# CON_PCIe_X4.net
KiCad netlist of a schematic drawn in Altium Designer
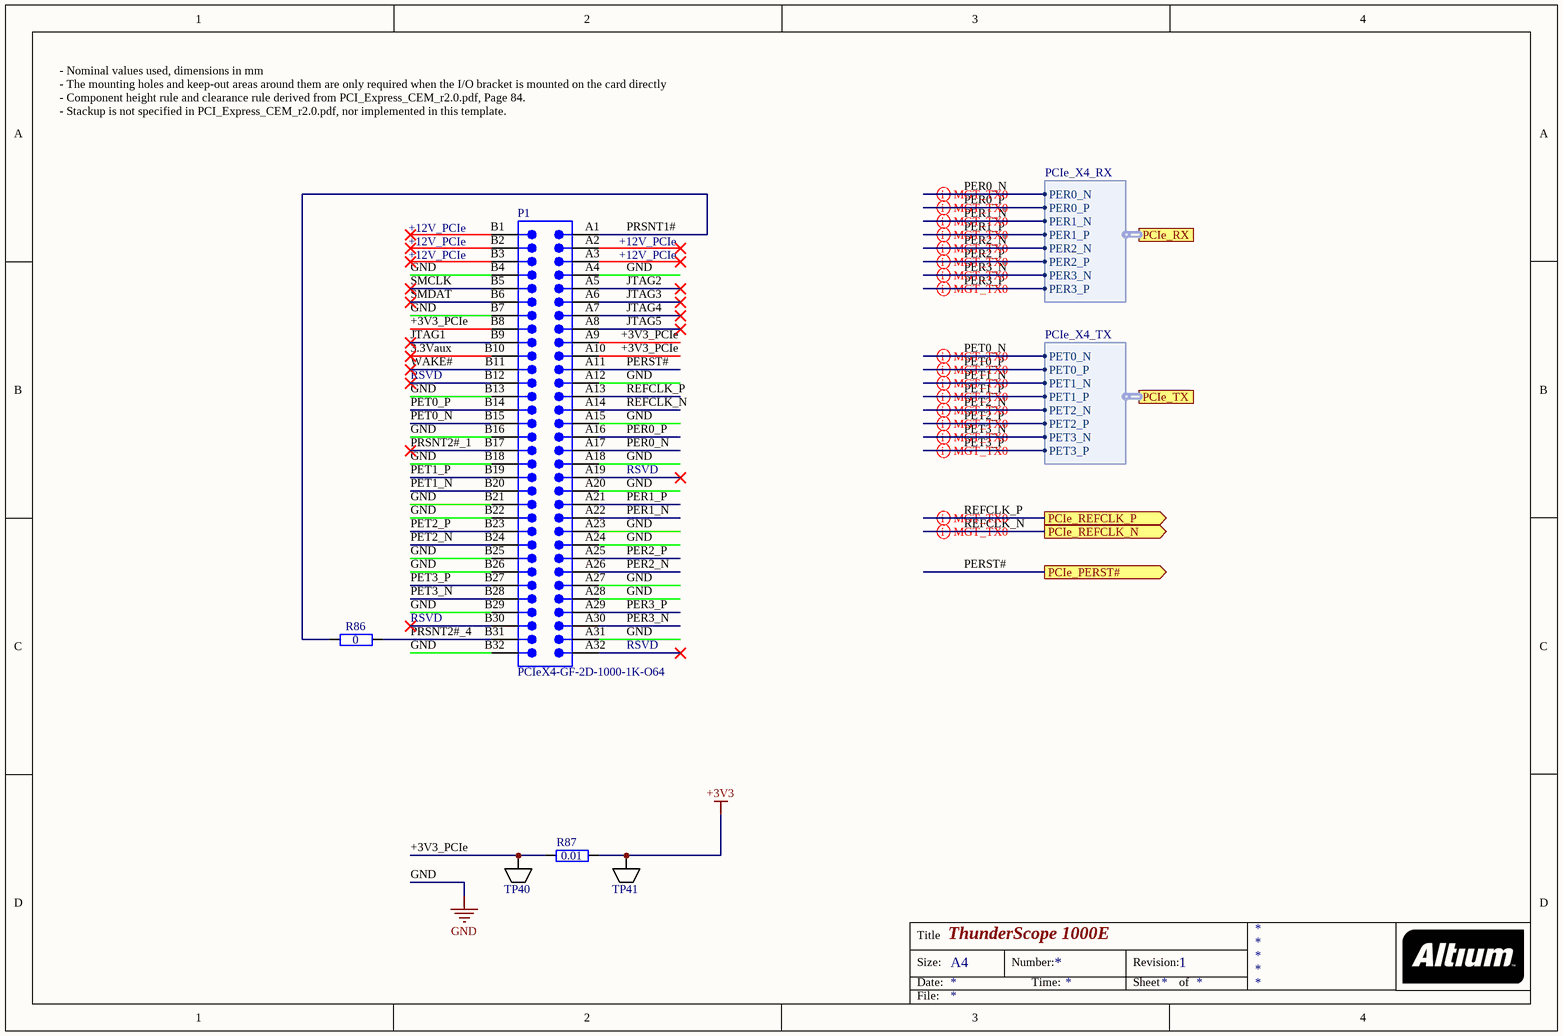
[diagram p0: CON_PCIe_X4.SchDoc]

(export (version "E")
  (design (tool "Eeschema 10.0.6"))
  (components
    (comp (ref "P1")
      (value "PCIeX4-GF-2D-1000-1K-O64")
      (footprint "PCIeX4-GF-2D-1000-1K-O64")
      (description "Golden finger, PCIeX4, Dual, Opposite, Pitch 1mm, 64-Position")
      (fields (field (name "PUBLISHER") "Altium"))
      (libsource (lib "Altium Content Vault") (part "PCIeX4-GF-2D-1000-1K-O64"))
    )
    (comp (ref "R86")
      (value "0")
      (footprint "GEN_R_0402")
      (libsource (lib "DSO") (part "RES 0 OHM 1/16W 0402"))
    )
    (comp (ref "R87")
      (value "0.01")
      (footprint "GEN_R_0603")
      (fields (field (name "TOLERANCE") "1%"))
      (libsource (lib "DSO") (part "RES 0.01 OHM 1% 1/4W 0603"))
    )
    (comp (ref "TP40")
      (value "5015")
      (footprint "KEY_5015")
      (libsource (lib "DSO") (part "TP KEYSTONE 5015"))
    )
    (comp (ref "TP41")
      (value "5015")
      (footprint "KEY_5015")
      (libsource (lib "DSO") (part "TP KEYSTONE 5015"))
    )
  )
  (nets
    (net (code "3") (name "+3V3") (class "Default")
      (node (ref "R87") (pin "2") (pinfunction "2_2") (pintype "passive"))
      (node (ref "TP41") (pin "1") (pinfunction "1_1") (pintype "passive"))
    )
    (net (code "4") (name "/+3V3_PCIe") (class "Default")
      (node (ref "P1") (pin "A10") (pinfunction "A10_A10") (pintype "passive"))
      (node (ref "P1") (pin "A9") (pinfunction "A9_A9") (pintype "passive"))
      (node (ref "P1") (pin "B8") (pinfunction "B8_B8") (pintype "passive"))
      (node (ref "R87") (pin "1") (pinfunction "1_1") (pintype "passive"))
      (node (ref "TP40") (pin "1") (pinfunction "1_1") (pintype "passive"))
    )
    (net (code "5") (name "/3.3Vaux") (class "Default")
      (node (ref "P1") (pin "B10") (pinfunction "B10_B10") (pintype "passive+no_connect"))
    )
    (net (code "6") (name "/JTAG1") (class "Default")
      (node (ref "P1") (pin "B9") (pinfunction "B9_B9") (pintype "passive+no_connect"))
    )
    (net (code "7") (name "/JTAG2") (class "Default")
      (node (ref "P1") (pin "A5") (pinfunction "A5_A5") (pintype "passive+no_connect"))
    )
    (net (code "8") (name "/JTAG3") (class "Default")
      (node (ref "P1") (pin "A6") (pinfunction "A6_A6") (pintype "passive+no_connect"))
    )
    (net (code "9") (name "/JTAG4") (class "Default")
      (node (ref "P1") (pin "A7") (pinfunction "A7_A7") (pintype "passive+no_connect"))
    )
    (net (code "10") (name "/JTAG5") (class "Default")
      (node (ref "P1") (pin "A8") (pinfunction "A8_A8") (pintype "passive+no_connect"))
    )
    (net (code "11") (name "/PER0_N") (class "Default")
      (node (ref "P1") (pin "A17") (pinfunction "A17_A17") (pintype "passive"))
    )
    (net (code "12") (name "/PER0_P") (class "Default")
      (node (ref "P1") (pin "A16") (pinfunction "A16_A16") (pintype "passive"))
    )
    (net (code "13") (name "/PER1_N") (class "Default")
      (node (ref "P1") (pin "A22") (pinfunction "A22_A22") (pintype "passive"))
    )
    (net (code "14") (name "/PER1_P") (class "Default")
      (node (ref "P1") (pin "A21") (pinfunction "A21_A21") (pintype "passive"))
    )
    (net (code "15") (name "/PER2_N") (class "Default")
      (node (ref "P1") (pin "A26") (pinfunction "A26_A26") (pintype "passive"))
    )
    (net (code "16") (name "/PER2_P") (class "Default")
      (node (ref "P1") (pin "A25") (pinfunction "A25_A25") (pintype "passive"))
    )
    (net (code "17") (name "/PER3_N") (class "Default")
      (node (ref "P1") (pin "A30") (pinfunction "A30_A30") (pintype "passive"))
    )
    (net (code "18") (name "/PER3_P") (class "Default")
      (node (ref "P1") (pin "A29") (pinfunction "A29_A29") (pintype "passive"))
    )
    (net (code "19") (name "/PERST#") (class "Default")
      (node (ref "P1") (pin "A11") (pinfunction "A11_A11") (pintype "passive"))
    )
    (net (code "20") (name "/PET0_N") (class "Default")
      (node (ref "P1") (pin "B15") (pinfunction "B15_B15") (pintype "passive"))
    )
    (net (code "21") (name "/PET0_P") (class "Default")
      (node (ref "P1") (pin "B14") (pinfunction "B14_B14") (pintype "passive"))
    )
    (net (code "22") (name "/PET1_N") (class "Default")
      (node (ref "P1") (pin "B20") (pinfunction "B20_B20") (pintype "passive"))
    )
    (net (code "23") (name "/PET1_P") (class "Default")
      (node (ref "P1") (pin "B19") (pinfunction "B19_B19") (pintype "passive"))
    )
    (net (code "24") (name "/PET2_N") (class "Default")
      (node (ref "P1") (pin "B24") (pinfunction "B24_B24") (pintype "passive"))
    )
    (net (code "25") (name "/PET2_P") (class "Default")
      (node (ref "P1") (pin "B23") (pinfunction "B23_B23") (pintype "passive"))
    )
    (net (code "26") (name "/PET3_N") (class "Default")
      (node (ref "P1") (pin "B28") (pinfunction "B28_B28") (pintype "passive"))
    )
    (net (code "27") (name "/PET3_P") (class "Default")
      (node (ref "P1") (pin "B27") (pinfunction "B27_B27") (pintype "passive"))
    )
    (net (code "28") (name "/PRSNT1#") (class "Default")
      (node (ref "P1") (pin "A1") (pinfunction "A1_A1") (pintype "passive"))
      (node (ref "R86") (pin "1") (pinfunction "1_1") (pintype "passive"))
    )
    (net (code "29") (name "/PRSNT2#_1") (class "Default")
      (node (ref "P1") (pin "B17") (pinfunction "B17_B17") (pintype "passive+no_connect"))
    )
    (net (code "30") (name "/PRSNT2#_4") (class "Default")
      (node (ref "P1") (pin "B31") (pinfunction "B31_B31") (pintype "passive"))
      (node (ref "R86") (pin "2") (pinfunction "2_2") (pintype "passive"))
    )
    (net (code "31") (name "/REFCLK_N") (class "Default")
      (node (ref "P1") (pin "A14") (pinfunction "A14_A14") (pintype "passive"))
    )
    (net (code "32") (name "/REFCLK_P") (class "Default")
      (node (ref "P1") (pin "A13") (pinfunction "A13_A13") (pintype "passive"))
    )
    (net (code "33") (name "/SMCLK") (class "Default")
      (node (ref "P1") (pin "B5") (pinfunction "B5_B5") (pintype "passive+no_connect"))
    )
    (net (code "34") (name "/SMDAT") (class "Default")
      (node (ref "P1") (pin "B6") (pinfunction "B6_B6") (pintype "passive+no_connect"))
    )
    (net (code "35") (name "/WAKE#") (class "Default")
      (node (ref "P1") (pin "B11") (pinfunction "B11_B11") (pintype "passive+no_connect"))
    )
    (net (code "38") (name "GND") (class "Default")
      (node (ref "P1") (pin "A12") (pinfunction "A12_A12") (pintype "passive"))
      (node (ref "P1") (pin "A15") (pinfunction "A15_A15") (pintype "passive"))
      (node (ref "P1") (pin "A18") (pinfunction "A18_A18") (pintype "passive"))
      (node (ref "P1") (pin "A20") (pinfunction "A20_A20") (pintype "passive"))
      (node (ref "P1") (pin "A23") (pinfunction "A23_A23") (pintype "passive"))
      (node (ref "P1") (pin "A24") (pinfunction "A24_A24") (pintype "passive"))
      (node (ref "P1") (pin "A27") (pinfunction "A27_A27") (pintype "passive"))
      (node (ref "P1") (pin "A28") (pinfunction "A28_A28") (pintype "passive"))
      (node (ref "P1") (pin "A31") (pinfunction "A31_A31") (pintype "passive"))
      (node (ref "P1") (pin "A4") (pinfunction "A4_A4") (pintype "passive"))
      (node (ref "P1") (pin "B13") (pinfunction "B13_B13") (pintype "passive"))
      (node (ref "P1") (pin "B16") (pinfunction "B16_B16") (pintype "passive"))
      (node (ref "P1") (pin "B18") (pinfunction "B18_B18") (pintype "passive"))
      (node (ref "P1") (pin "B21") (pinfunction "B21_B21") (pintype "passive"))
      (node (ref "P1") (pin "B22") (pinfunction "B22_B22") (pintype "passive"))
      (node (ref "P1") (pin "B25") (pinfunction "B25_B25") (pintype "passive"))
      (node (ref "P1") (pin "B26") (pinfunction "B26_B26") (pintype "passive"))
      (node (ref "P1") (pin "B29") (pinfunction "B29_B29") (pintype "passive"))
      (node (ref "P1") (pin "B32") (pinfunction "B32_B32") (pintype "passive"))
      (node (ref "P1") (pin "B4") (pinfunction "B4_B4") (pintype "passive"))
      (node (ref "P1") (pin "B7") (pinfunction "B7_B7") (pintype "passive"))
    )
    (net (code "39") (name "unconnected-(P1-PadA2)") (class "Default")
      (node (ref "P1") (pin "A2") (pinfunction "A2_A2") (pintype "passive+no_connect"))
    )
    (net (code "40") (name "unconnected-(P1-PadA3)") (class "Default")
      (node (ref "P1") (pin "A3") (pinfunction "A3_A3") (pintype "passive+no_connect"))
    )
    (net (code "41") (name "unconnected-(P1-PadA19)") (class "Default")
      (node (ref "P1") (pin "A19") (pinfunction "A19_A19") (pintype "passive+no_connect"))
    )
    (net (code "42") (name "unconnected-(P1-PadA32)") (class "Default")
      (node (ref "P1") (pin "A32") (pinfunction "A32_A32") (pintype "passive+no_connect"))
    )
    (net (code "43") (name "unconnected-(P1-PadB1)") (class "Default")
      (node (ref "P1") (pin "B1") (pinfunction "B1_B1") (pintype "passive+no_connect"))
    )
    (net (code "44") (name "unconnected-(P1-PadB2)") (class "Default")
      (node (ref "P1") (pin "B2") (pinfunction "B2_B2") (pintype "passive+no_connect"))
    )
    (net (code "45") (name "unconnected-(P1-PadB3)") (class "Default")
      (node (ref "P1") (pin "B3") (pinfunction "B3_B3") (pintype "passive+no_connect"))
    )
    (net (code "46") (name "unconnected-(P1-PadB12)") (class "Default")
      (node (ref "P1") (pin "B12") (pinfunction "B12_B12") (pintype "passive+no_connect"))
    )
    (net (code "47") (name "unconnected-(P1-PadB30)") (class "Default")
      (node (ref "P1") (pin "B30") (pinfunction "B30_B30") (pintype "passive+no_connect"))
    )
  )
)
